# PROC054D_FMCW_Sync.net
KiCad netlist of a schematic drawn in Altium Designer
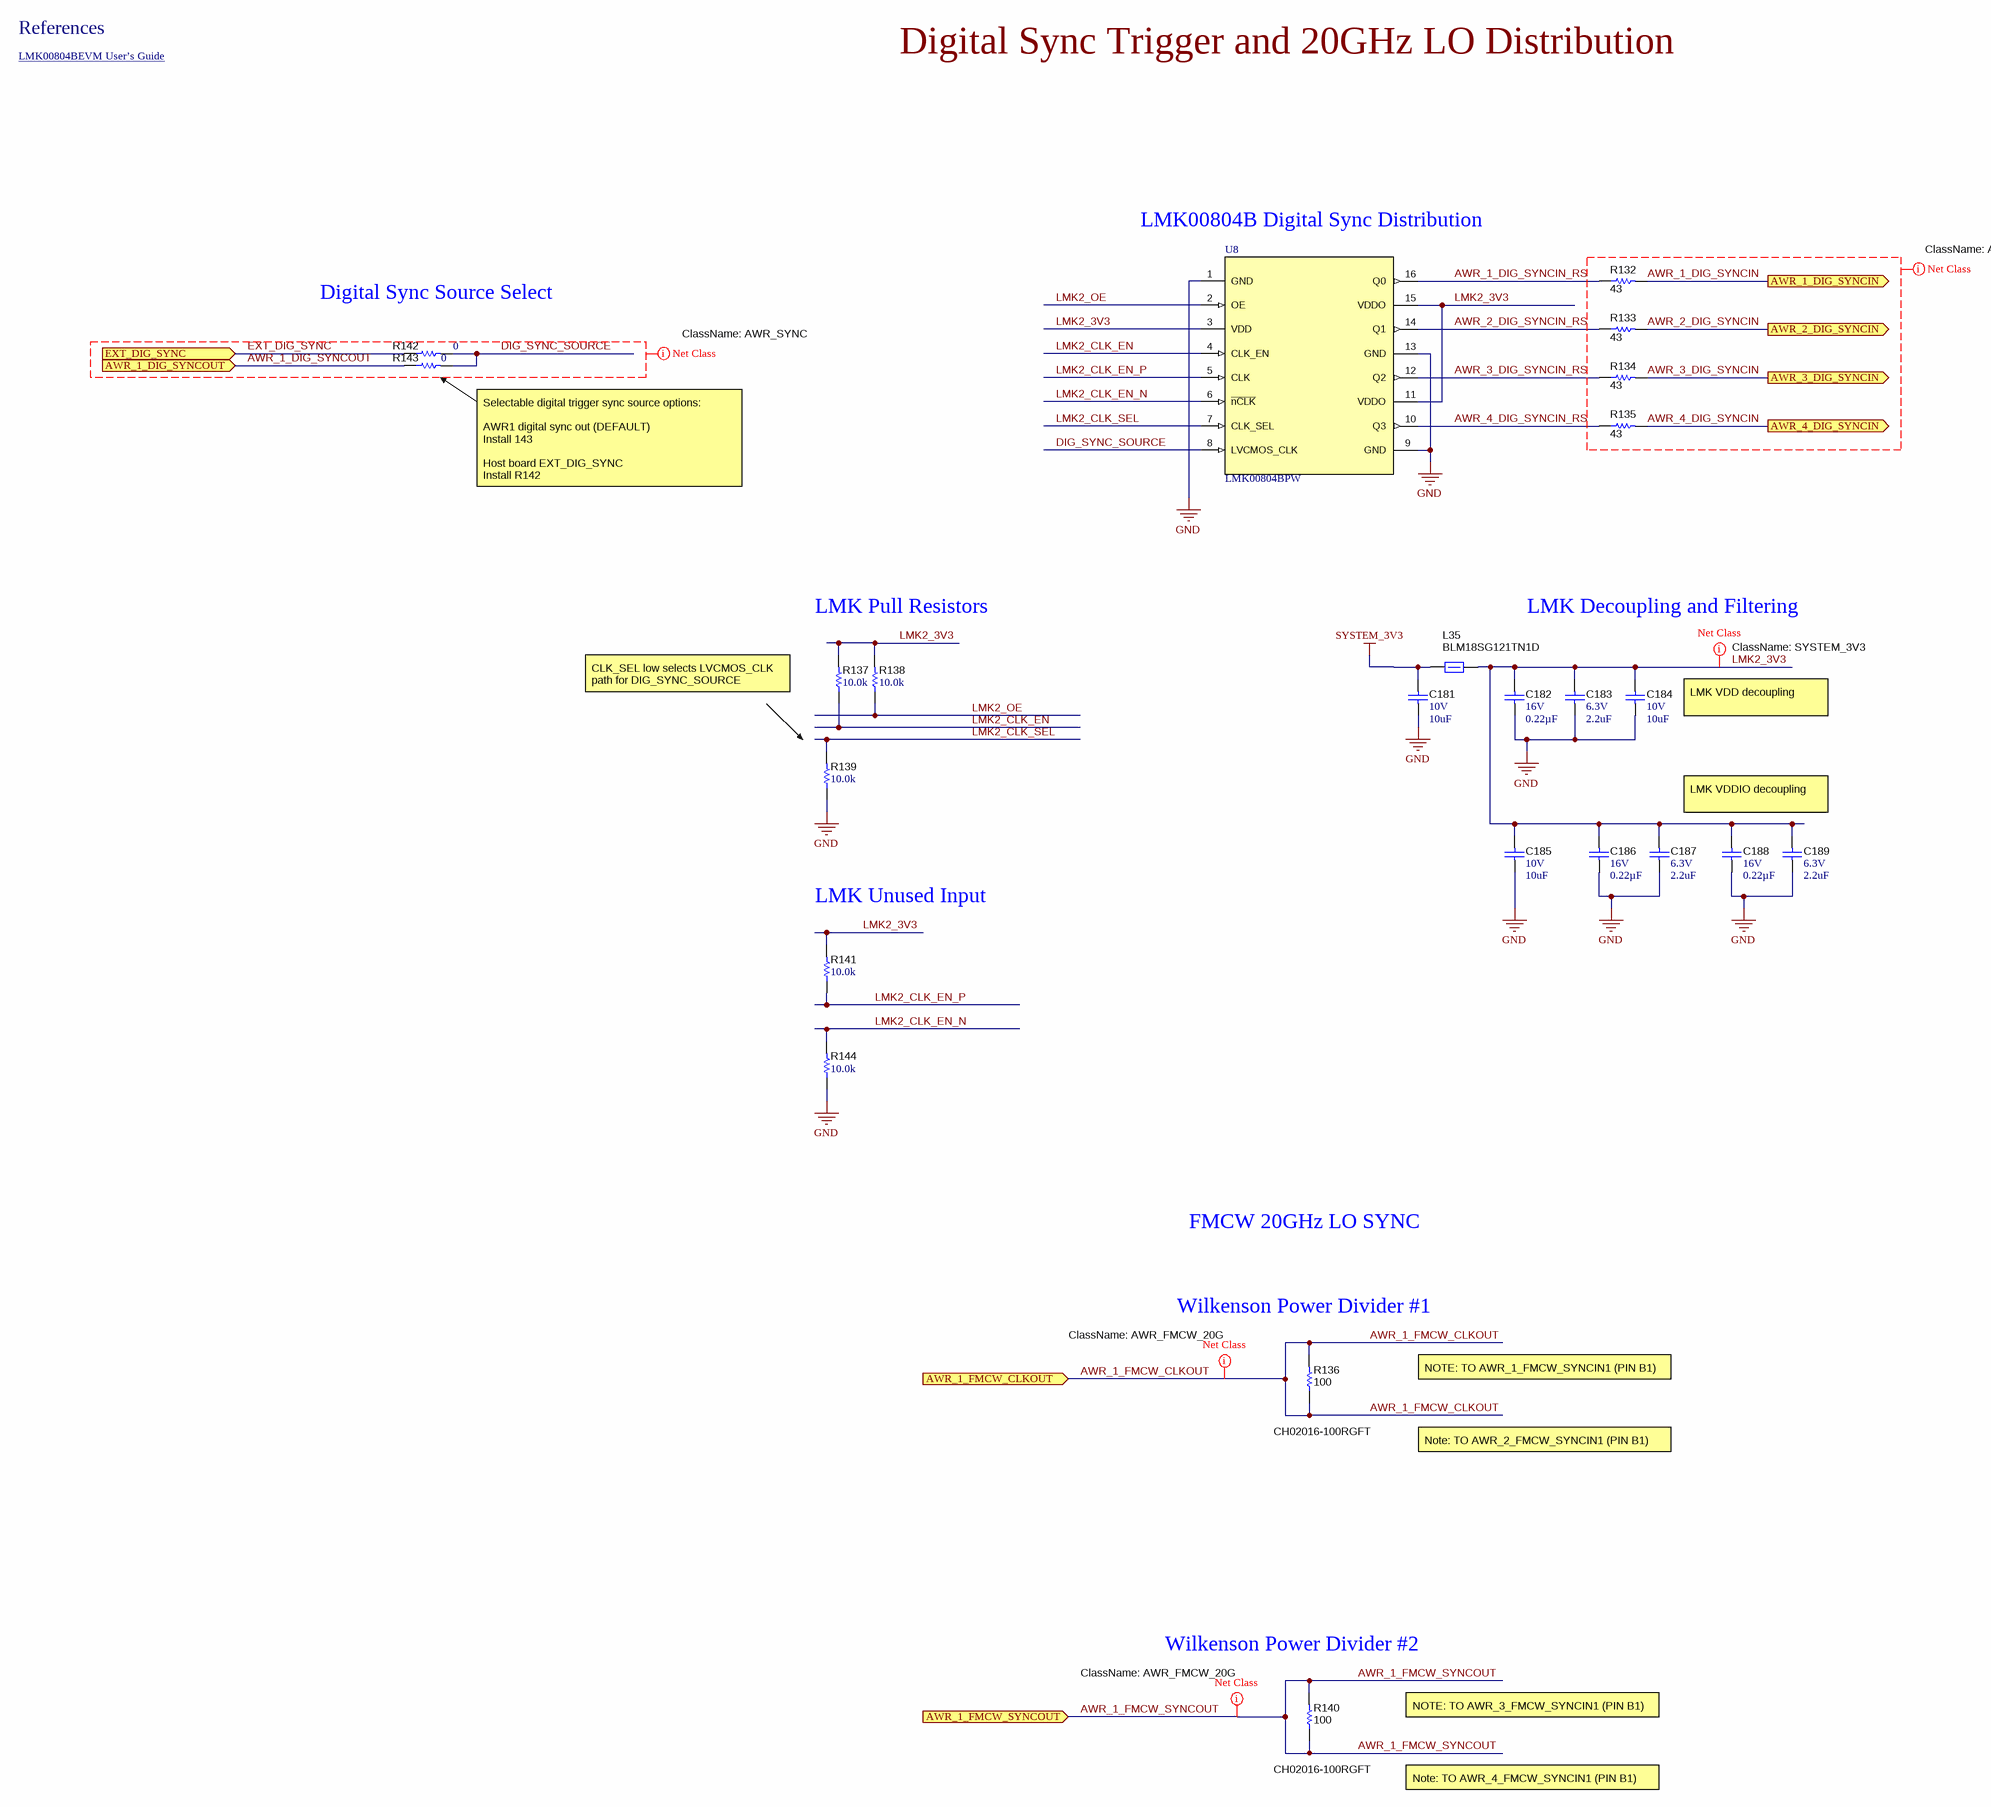
[diagram p0: PROC054D_FMCW_Sync.SchDoc]

(export (version "E")
  (design (tool "Eeschema 10.0.6"))
  (components
    (comp (ref "C181")
      (value "GCM21BR71A106KE22L")
      (footprint "0805_HV")
      (description "CAP, CERM, 10 uF, 10 V, +/- 10%, X7R, 0805")
      (fields
        (field (name "MANUFACTURER") "MuRata")
        (field (name "VDC_V") "10V")
        (field (name "VALUEDISPLAYED") "10uF")
        (field (name "PUBLISHER") "Texas Instruments")
      )
      (libsource (lib "Altium Vault - TI") (part "CMP-0008017-2"))
    )
    (comp (ref "C182")
      (value "GCM155R71C224KE02D")
      (footprint "0402")
      (description "CAP, CERM, 0.22 µF, 16 V,+/- 10%, X7R, AEC-Q200 Grade 1, 0402")
      (fields
        (field (name "MANUFACTURER") "MuRata")
        (field (name "VDC_V") "16V")
        (field (name "VALUEDISPLAYED") "0.22µF")
      )
      (libsource (lib "Altium Vault - TI") (part "CMP-0078265-1"))
    )
    (comp (ref "C183")
      (value "GCM188R70J225KE22D")
      (footprint "0603")
      (description "CAP, CERM, 2.2 uF, 6.3 V, +/- 10%, X7R, AEC-Q200 Grade 1, 0603")
      (fields
        (field (name "MANUFACTURER") "MuRata")
        (field (name "VDC_V") "6.3V")
        (field (name "VALUEDISPLAYED") "2.2uF")
        (field (name "PUBLISHER") "Texas Instruments")
      )
      (libsource (lib "Altium Vault - TI") (part "Capacitor"))
    )
    (comp (ref "C184")
      (value "GCM21BR71A106KE22L")
      (footprint "0805_HV")
      (description "CAP, CERM, 10 uF, 10 V, +/- 10%, X7R, 0805")
      (fields
        (field (name "MANUFACTURER") "MuRata")
        (field (name "VDC_V") "10V")
        (field (name "VALUEDISPLAYED") "10uF")
        (field (name "PUBLISHER") "Texas Instruments")
      )
      (libsource (lib "Altium Vault - TI") (part "CMP-0008017-2"))
    )
    (comp (ref "C185")
      (value "GCM21BR71A106KE22L")
      (footprint "0805_HV")
      (description "CAP, CERM, 10 uF, 10 V, +/- 10%, X7R, 0805")
      (fields
        (field (name "MANUFACTURER") "MuRata")
        (field (name "VDC_V") "10V")
        (field (name "VALUEDISPLAYED") "10uF")
        (field (name "PUBLISHER") "Texas Instruments")
      )
      (libsource (lib "Altium Vault - TI") (part "CMP-0008017-2"))
    )
    (comp (ref "C186")
      (value "GCM155R71C224KE02D")
      (footprint "0402")
      (description "CAP, CERM, 0.22 µF, 16 V,+/- 10%, X7R, AEC-Q200 Grade 1, 0402")
      (fields
        (field (name "MANUFACTURER") "MuRata")
        (field (name "VDC_V") "16V")
        (field (name "VALUEDISPLAYED") "0.22µF")
      )
      (libsource (lib "Altium Vault - TI") (part "CMP-0078265-1"))
    )
    (comp (ref "C187")
      (value "GCM188R70J225KE22D")
      (footprint "0603")
      (description "CAP, CERM, 2.2 uF, 6.3 V, +/- 10%, X7R, AEC-Q200 Grade 1, 0603")
      (fields
        (field (name "MANUFACTURER") "MuRata")
        (field (name "VDC_V") "6.3V")
        (field (name "VALUEDISPLAYED") "2.2uF")
        (field (name "PUBLISHER") "Texas Instruments")
      )
      (libsource (lib "Altium Vault - TI") (part "Capacitor"))
    )
    (comp (ref "C188")
      (value "GCM155R71C224KE02D")
      (footprint "0402")
      (description "CAP, CERM, 0.22 µF, 16 V,+/- 10%, X7R, AEC-Q200 Grade 1, 0402")
      (fields
        (field (name "MANUFACTURER") "MuRata")
        (field (name "VDC_V") "16V")
        (field (name "VALUEDISPLAYED") "0.22µF")
      )
      (libsource (lib "Altium Vault - TI") (part "CMP-0078265-1"))
    )
    (comp (ref "C189")
      (value "GCM188R70J225KE22D")
      (footprint "0603")
      (description "CAP, CERM, 2.2 uF, 6.3 V, +/- 10%, X7R, AEC-Q200 Grade 1, 0603")
      (fields
        (field (name "MANUFACTURER") "MuRata")
        (field (name "VDC_V") "6.3V")
        (field (name "VALUEDISPLAYED") "2.2uF")
        (field (name "PUBLISHER") "Texas Instruments")
      )
      (libsource (lib "Altium Vault - TI") (part "Capacitor"))
    )
    (comp (ref "L35")
      (value "BLM18SG121TN1D")
      (footprint "0603")
      (description "Ferrite Bead, 120 ohm @ 100 MHz, 3 A, 0603")
      (fields (field (name "MANUFACTURER") "MuRata") (field (name "PUBLISHER") "Texas Instruments"))
      (libsource (lib "Altium Vault - TI") (part "CMP-0003352-2"))
    )
    (comp (ref "R132")
      (value "CRCW040243R0JNED")
      (footprint "0402")
      (description "RES, 43, 5%, 0.063 W, AEC-Q200 Grade 0, 0402")
      (fields (field (name "MANUFACTURER") "Vishay-Dale") (field (name "VALUEDISPLAYED") "43"))
      (libsource (lib "Altium Vault - TI") (part "Resistor"))
    )
    (comp (ref "R133")
      (value "CRCW040243R0JNED")
      (footprint "0402")
      (description "RES, 43, 5%, 0.063 W, AEC-Q200 Grade 0, 0402")
      (fields (field (name "MANUFACTURER") "Vishay-Dale") (field (name "VALUEDISPLAYED") "43"))
      (libsource (lib "Altium Vault - TI") (part "Resistor"))
    )
    (comp (ref "R134")
      (value "CRCW040243R0JNED")
      (footprint "0402")
      (description "RES, 43, 5%, 0.063 W, AEC-Q200 Grade 0, 0402")
      (fields (field (name "MANUFACTURER") "Vishay-Dale") (field (name "VALUEDISPLAYED") "43"))
      (libsource (lib "Altium Vault - TI") (part "Resistor"))
    )
    (comp (ref "R135")
      (value "CRCW040243R0JNED")
      (footprint "0402")
      (description "RES, 43, 5%, 0.063 W, AEC-Q200 Grade 0, 0402")
      (fields (field (name "MANUFACTURER") "Vishay-Dale") (field (name "VALUEDISPLAYED") "43"))
      (libsource (lib "Altium Vault - TI") (part "Resistor"))
    )
    (comp (ref "R136")
      (value "CH02016-100RGFT")
      (footprint "02016")
      (description "RES, 100, 2%, 0.03 W, 02016")
      (fields
        (field (name "PARTNUMBER") "CH02016-100RGFT")
        (field (name "MANUFACTURER") "Vishay-Semiconductor")
        (field (name "VALUEDISPLAYED") "100")
      )
      (libsource (lib "Altium Vault - TI") (part "Resistor"))
    )
    (comp (ref "R137")
      (value "CRCW040210K0FKED")
      (footprint "0402")
      (description "RES, 10.0 k, 1%, 0.063 W, AEC-Q200 Grade 0, 0402")
      (fields (field (name "MANUFACTURER") "Vishay-Dale") (field (name "VALUEDISPLAYED") "10.0k"))
      (libsource (lib "Altium Vault - TI") (part "Resistor"))
    )
    (comp (ref "R138")
      (value "CRCW040210K0FKED")
      (footprint "0402")
      (description "RES, 10.0 k, 1%, 0.063 W, AEC-Q200 Grade 0, 0402")
      (fields (field (name "MANUFACTURER") "Vishay-Dale") (field (name "VALUEDISPLAYED") "10.0k"))
      (libsource (lib "Altium Vault - TI") (part "Resistor"))
    )
    (comp (ref "R139")
      (value "CRCW040210K0FKED")
      (footprint "0402")
      (description "RES, 10.0 k, 1%, 0.063 W, AEC-Q200 Grade 0, 0402")
      (fields (field (name "MANUFACTURER") "Vishay-Dale") (field (name "VALUEDISPLAYED") "10.0k"))
      (libsource (lib "Altium Vault - TI") (part "Resistor"))
    )
    (comp (ref "R140")
      (value "CH02016-100RGFT")
      (footprint "02016")
      (description "RES, 100, 2%, 0.03 W, 02016")
      (fields
        (field (name "PARTNUMBER") "CH02016-100RGFT")
        (field (name "MANUFACTURER") "Vishay-Semiconductor")
        (field (name "VALUEDISPLAYED") "100")
      )
      (libsource (lib "Altium Vault - TI") (part "Resistor"))
    )
    (comp (ref "R141")
      (value "CRCW040210K0FKED")
      (footprint "0402")
      (description "RES, 10.0 k, 1%, 0.063 W, AEC-Q200 Grade 0, 0402")
      (fields (field (name "MANUFACTURER") "Vishay-Dale") (field (name "VALUEDISPLAYED") "10.0k"))
      (libsource (lib "Altium Vault - TI") (part "Resistor"))
    )
    (comp (ref "R142")
      (value "ERJ-2GE0R00X")
      (footprint "0402")
      (description "RES, 0, 5%, 0.1 W, AEC-Q200 Grade 0, 0402")
      (fields (field (name "MANUFACTURER") "Panasonic") (field (name "VALUEDISPLAYED") "0"))
      (libsource (lib "Altium Vault - TI") (part "CMP-0026992-3"))
    )
    (comp (ref "R143")
      (value "ERJ-2GE0R00X")
      (footprint "0402")
      (description "RES, 0, 5%, 0.1 W, AEC-Q200 Grade 0, 0402")
      (fields (field (name "MANUFACTURER") "Panasonic") (field (name "VALUEDISPLAYED") "0"))
      (libsource (lib "Altium Vault - TI") (part "Resistor"))
    )
    (comp (ref "R144")
      (value "CRCW040210K0FKED")
      (footprint "0402")
      (description "RES, 10.0 k, 1%, 0.063 W, AEC-Q200 Grade 0, 0402")
      (fields (field (name "MANUFACTURER") "Vishay-Dale") (field (name "VALUEDISPLAYED") "10.0k"))
      (libsource (lib "Altium Vault - TI") (part "Resistor"))
    )
    (comp (ref "U8")
      (value "LMK00804BPW")
      (footprint "PW0016A_N")
      (description "Low Skew, 1-to-4 Multiplexed Differential/LVCMOS-to-LVCMOS/TTL Fanout Buffer, PW0016A (TSSOP-16)")
      (fields
        (field (name "MANUFACTURER") "Texas Instruments")
        (field (name "PARTNUMBER") "LMK00804BPW")
        (field (name "PUBLISHER") "Texas Instruments")
      )
      (libsource (lib "Altium Vault - TI") (part "CMP-0065663-1"))
    )
  )
  (nets
    (net (code "1") (name "/AWR_1_DIG_SYNCIN") (class "Default")
      (node (ref "R132") (pin "2") (pinfunction "2_2") (pintype "passive"))
    )
    (net (code "2") (name "/AWR_1_DIG_SYNCIN_RS") (class "Default")
      (node (ref "R132") (pin "1") (pinfunction "1_1") (pintype "passive"))
      (node (ref "U8") (pin "16") (pinfunction "Q0_16") (pintype "output"))
    )
    (net (code "3") (name "/AWR_1_DIG_SYNCOUT") (class "Default")
      (node (ref "R143") (pin "1") (pinfunction "1_1") (pintype "passive"))
    )
    (net (code "4") (name "/AWR_1_FMCW_CLKOUT") (class "Default")
      (node (ref "R136") (pin "1") (pinfunction "1_1") (pintype "passive"))
      (node (ref "R136") (pin "2") (pinfunction "2_2") (pintype "passive"))
    )
    (net (code "5") (name "/AWR_1_FMCW_SYNCOUT") (class "Default")
      (node (ref "R140") (pin "1") (pinfunction "1_1") (pintype "passive"))
      (node (ref "R140") (pin "2") (pinfunction "2_2") (pintype "passive"))
    )
    (net (code "6") (name "/AWR_2_DIG_SYNCIN") (class "Default")
      (node (ref "R133") (pin "2") (pinfunction "2_2") (pintype "passive"))
    )
    (net (code "7") (name "/AWR_2_DIG_SYNCIN_RS") (class "Default")
      (node (ref "R133") (pin "1") (pinfunction "1_1") (pintype "passive"))
      (node (ref "U8") (pin "14") (pinfunction "Q1_14") (pintype "output"))
    )
    (net (code "8") (name "/AWR_3_DIG_SYNCIN") (class "Default")
      (node (ref "R134") (pin "2") (pinfunction "2_2") (pintype "passive"))
    )
    (net (code "9") (name "/AWR_3_DIG_SYNCIN_RS") (class "Default")
      (node (ref "R134") (pin "1") (pinfunction "1_1") (pintype "passive"))
      (node (ref "U8") (pin "12") (pinfunction "Q2_12") (pintype "output"))
    )
    (net (code "10") (name "/AWR_4_DIG_SYNCIN") (class "Default")
      (node (ref "R135") (pin "2") (pinfunction "2_2") (pintype "passive"))
    )
    (net (code "11") (name "/AWR_4_DIG_SYNCIN_RS") (class "Default")
      (node (ref "R135") (pin "1") (pinfunction "1_1") (pintype "passive"))
      (node (ref "U8") (pin "10") (pinfunction "Q3_10") (pintype "output"))
    )
    (net (code "12") (name "/DIG_SYNC_SOURCE") (class "Default")
      (node (ref "R142") (pin "2") (pinfunction "2_2") (pintype "passive"))
      (node (ref "R143") (pin "2") (pinfunction "2_2") (pintype "passive"))
      (node (ref "U8") (pin "8") (pinfunction "LVCMOS_CLK_8") (pintype "input"))
    )
    (net (code "13") (name "/EXT_DIG_SYNC") (class "Default")
      (node (ref "R142") (pin "1") (pinfunction "1_1") (pintype "passive"))
    )
    (net (code "14") (name "/LMK2_3V3") (class "Default")
      (node (ref "C182") (pin "1") (pinfunction "1_1") (pintype "passive"))
      (node (ref "C183") (pin "2") (pinfunction "2_2") (pintype "passive"))
      (node (ref "C184") (pin "1") (pinfunction "1_1") (pintype "passive"))
      (node (ref "C185") (pin "1") (pinfunction "1_1") (pintype "passive"))
      (node (ref "C186") (pin "1") (pinfunction "1_1") (pintype "passive"))
      (node (ref "C187") (pin "2") (pinfunction "2_2") (pintype "passive"))
      (node (ref "C188") (pin "1") (pinfunction "1_1") (pintype "passive"))
      (node (ref "C189") (pin "2") (pinfunction "2_2") (pintype "passive"))
      (node (ref "L35") (pin "2") (pinfunction "2_2") (pintype "passive"))
      (node (ref "R137") (pin "2") (pinfunction "2_2") (pintype "passive"))
      (node (ref "R138") (pin "2") (pinfunction "2_2") (pintype "passive"))
      (node (ref "R141") (pin "2") (pinfunction "2_2") (pintype "passive"))
      (node (ref "U8") (pin "11") (pinfunction "VDDO_11") (pintype "power_in"))
      (node (ref "U8") (pin "15") (pinfunction "VDDO_15") (pintype "power_in"))
      (node (ref "U8") (pin "3") (pinfunction "VDD_3") (pintype "power_in"))
    )
    (net (code "15") (name "/LMK2_CLK_EN") (class "Default")
      (node (ref "R137") (pin "1") (pinfunction "1_1") (pintype "passive"))
      (node (ref "U8") (pin "4") (pinfunction "CLK_EN_4") (pintype "input"))
    )
    (net (code "16") (name "/LMK2_CLK_EN_N") (class "Default")
      (node (ref "R144") (pin "2") (pinfunction "2_2") (pintype "passive"))
      (node (ref "U8") (pin "6") (pinfunction "nCLK_6") (pintype "input"))
    )
    (net (code "17") (name "/LMK2_CLK_EN_P") (class "Default")
      (node (ref "R141") (pin "1") (pinfunction "1_1") (pintype "passive"))
      (node (ref "U8") (pin "5") (pinfunction "CLK_5") (pintype "input"))
    )
    (net (code "18") (name "/LMK2_CLK_SEL") (class "Default")
      (node (ref "R139") (pin "2") (pinfunction "2_2") (pintype "passive"))
      (node (ref "U8") (pin "7") (pinfunction "CLK_SEL_7") (pintype "input"))
    )
    (net (code "19") (name "/LMK2_OE") (class "Default")
      (node (ref "R138") (pin "1") (pinfunction "1_1") (pintype "passive"))
      (node (ref "U8") (pin "2") (pinfunction "OE_2") (pintype "input"))
    )
    (net (code "20") (name "GND") (class "Default")
      (node (ref "C181") (pin "2") (pinfunction "2_2") (pintype "passive"))
      (node (ref "C182") (pin "2") (pinfunction "2_2") (pintype "passive"))
      (node (ref "C183") (pin "1") (pinfunction "1_1") (pintype "passive"))
      (node (ref "C184") (pin "2") (pinfunction "2_2") (pintype "passive"))
      (node (ref "C185") (pin "2") (pinfunction "2_2") (pintype "passive"))
      (node (ref "C186") (pin "2") (pinfunction "2_2") (pintype "passive"))
      (node (ref "C187") (pin "1") (pinfunction "1_1") (pintype "passive"))
      (node (ref "C188") (pin "2") (pinfunction "2_2") (pintype "passive"))
      (node (ref "C189") (pin "1") (pinfunction "1_1") (pintype "passive"))
      (node (ref "R139") (pin "1") (pinfunction "1_1") (pintype "passive"))
      (node (ref "R144") (pin "1") (pinfunction "1_1") (pintype "passive"))
      (node (ref "U8") (pin "1") (pinfunction "GND_1") (pintype "power_in"))
      (node (ref "U8") (pin "13") (pinfunction "GND_13") (pintype "power_in"))
      (node (ref "U8") (pin "9") (pinfunction "GND_9") (pintype "power_in"))
    )
    (net (code "21") (name "SYSTEM_3V3") (class "Default")
      (node (ref "C181") (pin "1") (pinfunction "1_1") (pintype "passive"))
      (node (ref "L35") (pin "1") (pinfunction "1_1") (pintype "passive"))
    )
  )
)
